# OPA1622_-_Buffer.net
KiCad netlist of a schematic drawn in EAGLE
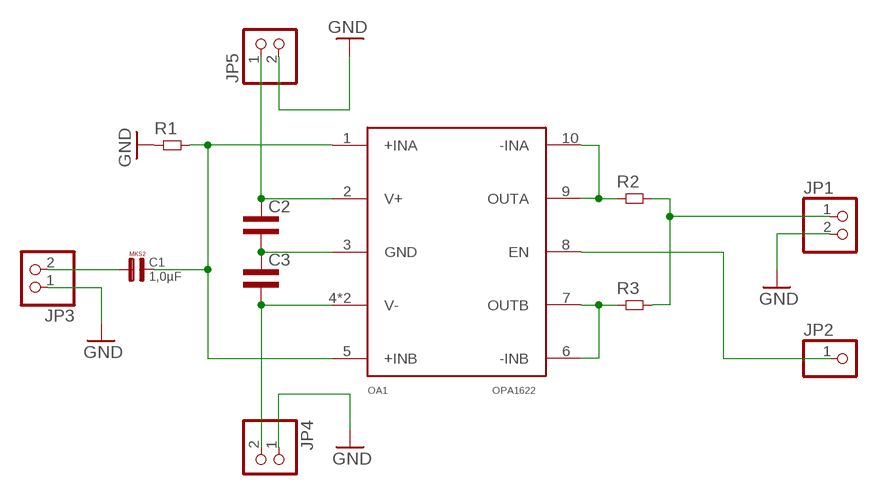
[diagram p0: schematic, sheet 1]

(export (version "E")
  (design (tool "Eeschema 10.0.6"))
  (components
    (comp (ref "C1")
      (value "1,0µF")
      (footprint "eagle-import:R5B5")
      (libsource (lib "eagle-import") (part "1,0µF"))
    )
    (comp (ref "C2")
      (value "CAP0603L3")
      (footprint "eagle-import:0603L3")
      (libsource (lib "eagle-import") (part "CAP0603L3"))
    )
    (comp (ref "C3")
      (value "CAP0603L3")
      (footprint "eagle-import:0603L3")
      (libsource (lib "eagle-import") (part "CAP0603L3"))
    )
    (comp (ref "JP1")
      (value "PINHD-1X2")
      (footprint "eagle-import:1X02")
      (libsource (lib "eagle-import") (part "PINHD-1X2"))
    )
    (comp (ref "JP2")
      (value "PINHD-1X1")
      (footprint "eagle-import:1X01")
      (libsource (lib "eagle-import") (part "PINHD-1X1"))
    )
    (comp (ref "JP3")
      (value "PINHD-1X2")
      (footprint "eagle-import:1X02")
      (libsource (lib "eagle-import") (part "PINHD-1X2"))
    )
    (comp (ref "JP4")
      (value "PINHD-1X2")
      (footprint "eagle-import:1X02")
      (libsource (lib "eagle-import") (part "PINHD-1X2"))
    )
    (comp (ref "JP5")
      (value "PINHD-1X2")
      (footprint "eagle-import:1X02")
      (libsource (lib "eagle-import") (part "PINHD-1X2"))
    )
    (comp (ref "OA1")
      (value "OPA1622")
      (footprint "eagle-import:S-PVSON-N10")
      (libsource (lib "eagle-import") (part "OPA1622"))
    )
    (comp (ref "R1")
      (value "RES0603L3")
      (footprint "eagle-import:0603L3")
      (libsource (lib "eagle-import") (part "RES0603L3"))
    )
    (comp (ref "R2")
      (value "RES0805L3")
      (footprint "eagle-import:0805L3")
      (libsource (lib "eagle-import") (part "RES0805L3"))
    )
    (comp (ref "R3")
      (value "RES0805L3")
      (footprint "eagle-import:0805L3")
      (libsource (lib "eagle-import") (part "RES0805L3"))
    )
  )
  (nets
    (net (code "1") (name "GND") (class "Default")
      (node (ref "JP1") (pin "2") (pinfunction "2_2") (pintype "passive"))
      (node (ref "JP3") (pin "1") (pinfunction "1_1") (pintype "passive"))
      (node (ref "JP4") (pin "1") (pinfunction "1_1") (pintype "passive"))
      (node (ref "JP5") (pin "2") (pinfunction "2_2") (pintype "passive"))
      (node (ref "R1") (pin "P$1") (pinfunction "1_P$1") (pintype "bidirectional"))
    )
    (net (code "2") (name "Net-(C1-Pad1)") (class "Default")
      (node (ref "C1") (pin "1") (pinfunction "1_1") (pintype "passive"))
      (node (ref "JP3") (pin "2") (pinfunction "2_2") (pintype "passive"))
    )
    (net (code "3") (name "Net-(C2-1)") (class "Default")
      (node (ref "C2") (pin "P$1") (pinfunction "1_P$1") (pintype "bidirectional"))
      (node (ref "JP5") (pin "1") (pinfunction "1_1") (pintype "passive"))
      (node (ref "OA1") (pin "2") (pinfunction "V+_2") (pintype "bidirectional"))
    )
    (net (code "4") (name "Net-(C2-2)") (class "Default")
      (node (ref "C2") (pin "P$2") (pinfunction "2_P$2") (pintype "bidirectional"))
      (node (ref "C3") (pin "P$1") (pinfunction "1_P$1") (pintype "bidirectional"))
      (node (ref "OA1") (pin "3") (pinfunction "GND_3") (pintype "bidirectional"))
    )
    (net (code "5") (name "Net-(C3-2)") (class "Default")
      (node (ref "C3") (pin "P$2") (pinfunction "2_P$2") (pintype "bidirectional"))
      (node (ref "JP4") (pin "2") (pinfunction "2_2") (pintype "passive"))
      (node (ref "OA1") (pin "4") (pinfunction "V-_4") (pintype "bidirectional"))
      (node (ref "OA1") (pin "TP") (pinfunction "V-_TP") (pintype "bidirectional"))
    )
    (net (code "6") (name "Net-(JP1-Pad1)") (class "Default")
      (node (ref "JP1") (pin "1") (pinfunction "1_1") (pintype "passive"))
      (node (ref "R2") (pin "2") (pinfunction "2_2") (pintype "bidirectional"))
      (node (ref "R3") (pin "2") (pinfunction "2_2") (pintype "bidirectional"))
    )
    (net (code "7") (name "Net-(OA1-+INA)") (class "Default")
      (node (ref "C1") (pin "2") (pinfunction "2_2") (pintype "passive"))
      (node (ref "OA1") (pin "1") (pinfunction "+INA_1") (pintype "bidirectional"))
      (node (ref "OA1") (pin "5") (pinfunction "+INB_5") (pintype "bidirectional"))
      (node (ref "R1") (pin "P$2") (pinfunction "2_P$2") (pintype "bidirectional"))
    )
    (net (code "8") (name "Net-(OA1--INA)") (class "Default")
      (node (ref "OA1") (pin "10") (pinfunction "-INA_10") (pintype "bidirectional"))
      (node (ref "OA1") (pin "9") (pinfunction "OUTA_9") (pintype "bidirectional"))
      (node (ref "R2") (pin "1") (pinfunction "1_1") (pintype "bidirectional"))
    )
    (net (code "9") (name "Net-(OA1--INB)") (class "Default")
      (node (ref "OA1") (pin "6") (pinfunction "-INB_6") (pintype "bidirectional"))
      (node (ref "OA1") (pin "7") (pinfunction "OUTB_7") (pintype "bidirectional"))
      (node (ref "R3") (pin "1") (pinfunction "1_1") (pintype "bidirectional"))
    )
    (net (code "10") (name "Net-(OA1-EN)") (class "Default")
      (node (ref "JP2") (pin "1") (pinfunction "1_1") (pintype "passive"))
      (node (ref "OA1") (pin "8") (pinfunction "EN_8") (pintype "bidirectional"))
    )
  )
)
